# OPT3001.net
KiCad netlist of a schematic drawn in Altium Designer
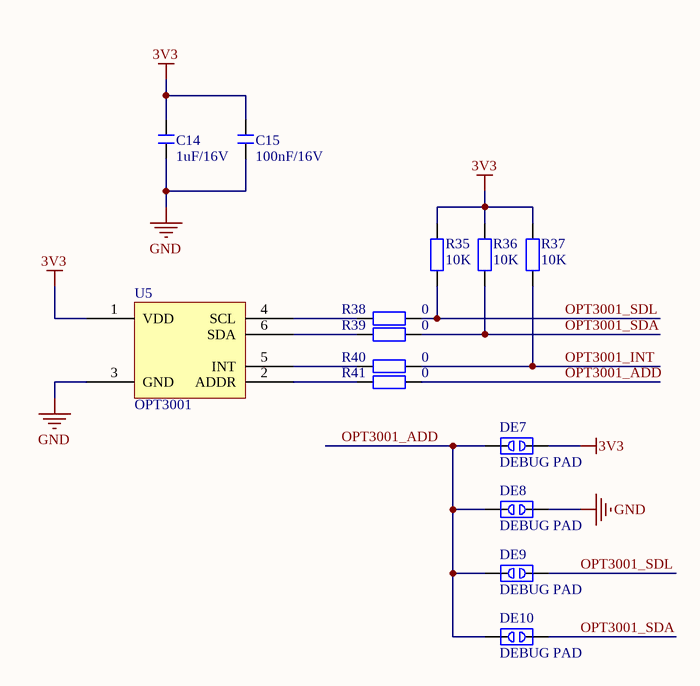
[diagram p0: OPT3001.SchDoc]

(export (version "E")
  (design (tool "Eeschema 10.0.6"))
  (components
    (comp (ref "C14")
      (value "1uF/16V")
      (footprint "C 0402_L")
      (description "贴片电容")
      (libsource (lib "3.1   - 电阻-电容-电感") (part "C"))
    )
    (comp (ref "C15")
      (value "100nF/16V")
      (footprint "C 0402_L")
      (description "无极性贴片电容")
      (libsource (lib "3.1   - 电阻-电容-电感") (part "C"))
    )
    (comp (ref "DE7")
      (value "DEBUG PAD")
      (footprint "DEBUG_A")
      (description "调试断点焊盘")
      (fields (field (name "版权归属") "源创客"))
      (libsource (lib "15.1 - 未分类器件") (part "DEBUG"))
    )
    (comp (ref "DE8")
      (value "DEBUG PAD")
      (footprint "DEBUG_A")
      (description "调试断点焊盘")
      (fields (field (name "版权归属") "源创客"))
      (libsource (lib "15.1 - 未分类器件") (part "DEBUG"))
    )
    (comp (ref "DE9")
      (value "DEBUG PAD")
      (footprint "DEBUG_A")
      (description "调试断点焊盘")
      (fields (field (name "版权归属") "源创客"))
      (libsource (lib "15.1 - 未分类器件") (part "DEBUG"))
    )
    (comp (ref "DE10")
      (value "DEBUG PAD")
      (footprint "DEBUG_A")
      (description "调试断点焊盘")
      (fields (field (name "版权归属") "源创客"))
      (libsource (lib "15.1 - 未分类器件") (part "DEBUG"))
    )
    (comp (ref "R35")
      (value "10K")
      (footprint "R 0402_L")
      (description "贴片电阻 0402 1%")
      (libsource (lib "3.1   - 电阻-电容-电感") (part "R"))
    )
    (comp (ref "R36")
      (value "10K")
      (footprint "R 0402_L")
      (description "贴片电阻 0402 1%")
      (libsource (lib "3.1   - 电阻-电容-电感") (part "R"))
    )
    (comp (ref "R37")
      (value "10K")
      (footprint "R 0402_L")
      (description "贴片电阻 0402 1%")
      (libsource (lib "3.1   - 电阻-电容-电感") (part "R"))
    )
    (comp (ref "R38")
      (value "0")
      (footprint "R 0402_L")
      (description "贴片电阻")
      (libsource (lib "3.1   - 电阻-电容-电感") (part "R"))
    )
    (comp (ref "R39")
      (value "0")
      (footprint "R 0402_L")
      (description "贴片电阻")
      (libsource (lib "3.1   - 电阻-电容-电感") (part "R"))
    )
    (comp (ref "R40")
      (value "0")
      (footprint "R 0402_L")
      (description "贴片电阻")
      (libsource (lib "3.1   - 电阻-电容-电感") (part "R"))
    )
    (comp (ref "R41")
      (value "0")
      (footprint "R 0402_L")
      (description "贴片电阻")
      (libsource (lib "3.1   - 电阻-电容-电感") (part "R"))
    )
    (comp (ref "U5") (value "OPT3001") (footprint "OPT3001") (libsource (lib "Schlib1") (part "OPT3001")))
  )
  (nets
    (net (code "1") (name "/OPT3001_ADD") (class "Default")
      (node (ref "DE10") (pin "1") (pinfunction "1_1") (pintype "passive"))
      (node (ref "DE7") (pin "1") (pinfunction "1_1") (pintype "passive"))
      (node (ref "DE8") (pin "1") (pinfunction "1_1") (pintype "passive"))
      (node (ref "DE9") (pin "1") (pinfunction "1_1") (pintype "passive"))
      (node (ref "R41") (pin "1") (pinfunction "1_1") (pintype "passive"))
    )
    (net (code "2") (name "/OPT3001_INT") (class "Default")
      (node (ref "R37") (pin "2") (pinfunction "2_2") (pintype "passive"))
      (node (ref "R40") (pin "1") (pinfunction "1_1") (pintype "passive"))
    )
    (net (code "3") (name "/OPT3001_SDA") (class "Default")
      (node (ref "DE10") (pin "2") (pinfunction "2_2") (pintype "passive"))
      (node (ref "R36") (pin "2") (pinfunction "2_2") (pintype "passive"))
      (node (ref "R39") (pin "1") (pinfunction "1_1") (pintype "passive"))
    )
    (net (code "4") (name "/OPT3001_SDL") (class "Default")
      (node (ref "DE9") (pin "2") (pinfunction "2_2") (pintype "passive"))
      (node (ref "R35") (pin "2") (pinfunction "2_2") (pintype "passive"))
      (node (ref "R38") (pin "1") (pinfunction "1_1") (pintype "passive"))
    )
    (net (code "5") (name "3V3") (class "Default")
      (node (ref "C14") (pin "2") (pinfunction "2_2") (pintype "passive"))
      (node (ref "C15") (pin "1") (pinfunction "1_1") (pintype "passive"))
      (node (ref "DE7") (pin "2") (pinfunction "2_2") (pintype "passive"))
      (node (ref "R35") (pin "1") (pinfunction "1_1") (pintype "passive"))
      (node (ref "R36") (pin "1") (pinfunction "1_1") (pintype "passive"))
      (node (ref "R37") (pin "1") (pinfunction "1_1") (pintype "passive"))
      (node (ref "U5") (pin "1") (pinfunction "VDD_1") (pintype "passive"))
    )
    (net (code "6") (name "GND") (class "Default")
      (node (ref "C14") (pin "1") (pinfunction "1_1") (pintype "passive"))
      (node (ref "C15") (pin "2") (pinfunction "2_2") (pintype "passive"))
      (node (ref "DE8") (pin "2") (pinfunction "2_2") (pintype "passive"))
      (node (ref "U5") (pin "3") (pinfunction "GND_3") (pintype "passive"))
    )
    (net (code "7") (name "Net-(U5-ADDR)") (class "Default")
      (node (ref "R41") (pin "2") (pinfunction "2_2") (pintype "passive"))
      (node (ref "U5") (pin "2") (pinfunction "ADDR_2") (pintype "passive"))
    )
    (net (code "8") (name "Net-(U5-INT)") (class "Default")
      (node (ref "R40") (pin "2") (pinfunction "2_2") (pintype "passive"))
      (node (ref "U5") (pin "5") (pinfunction "INT_5") (pintype "passive"))
    )
    (net (code "9") (name "Net-(U5-SCL)") (class "Default")
      (node (ref "R38") (pin "2") (pinfunction "2_2") (pintype "passive"))
      (node (ref "U5") (pin "4") (pinfunction "SCL_4") (pintype "passive"))
    )
    (net (code "10") (name "Net-(U5-SDA)") (class "Default")
      (node (ref "R39") (pin "2") (pinfunction "2_2") (pintype "passive"))
      (node (ref "U5") (pin "6") (pinfunction "SDA_6") (pintype "passive"))
    )
  )
)
